# Power.net
KiCad netlist of a schematic drawn in Altium Designer
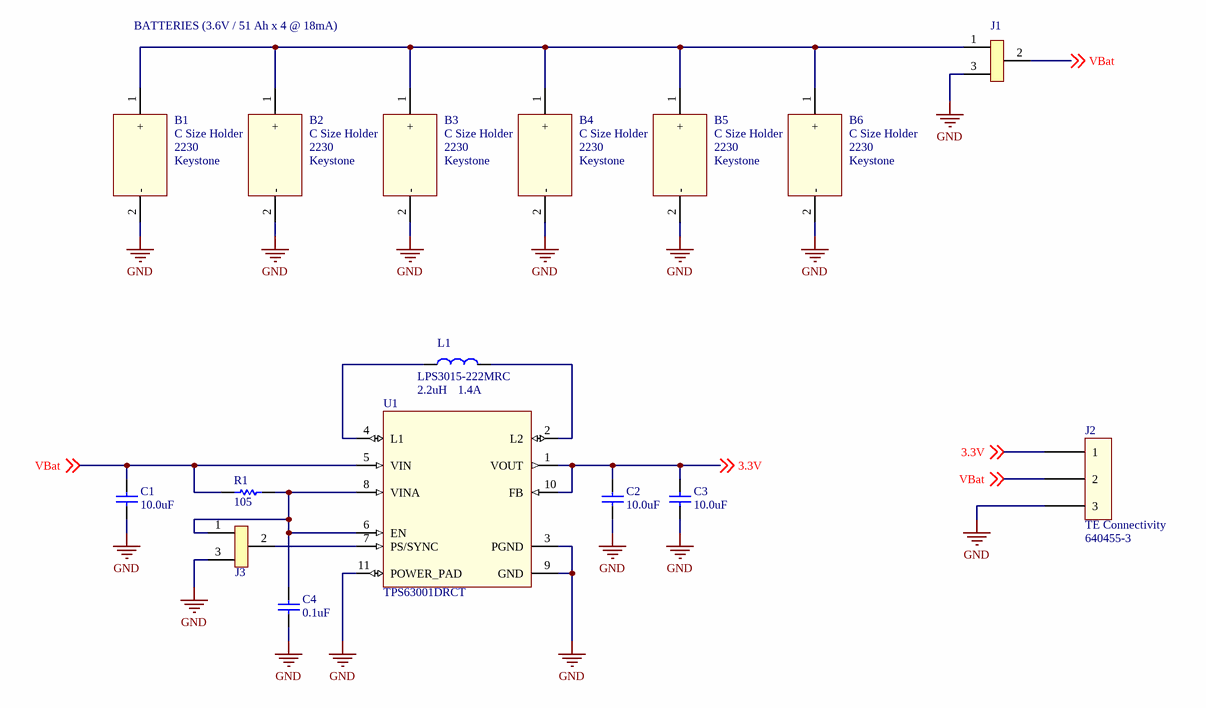
[diagram p0: Power.SchDoc]

(export (version "E")
  (design (tool "Eeschema 10.0.6"))
  (components
    (comp (ref "B1")
      (value "C Size Holder")
      (footprint "KEYSTONE-2230")
      (fields
        (field (name "PARTNUMBER") "2230")
        (field (name "MANUFACTURER") "Keystone")
        (field (name "Comment") "2230")
      )
      (libsource (lib "Keystone") (part "2230"))
    )
    (comp (ref "B2")
      (value "C Size Holder")
      (footprint "KEYSTONE-2230")
      (fields
        (field (name "PARTNUMBER") "2230")
        (field (name "MANUFACTURER") "Keystone")
        (field (name "Comment") "2230")
      )
      (libsource (lib "Keystone") (part "2230"))
    )
    (comp (ref "B3")
      (value "C Size Holder")
      (footprint "KEYSTONE-2230")
      (fields
        (field (name "PARTNUMBER") "2230")
        (field (name "MANUFACTURER") "Keystone")
        (field (name "Comment") "2230")
      )
      (libsource (lib "Keystone") (part "2230"))
    )
    (comp (ref "B4")
      (value "C Size Holder")
      (footprint "KEYSTONE-2230")
      (fields
        (field (name "PARTNUMBER") "2230")
        (field (name "MANUFACTURER") "Keystone")
        (field (name "Comment") "2230")
      )
      (libsource (lib "Keystone") (part "2230"))
    )
    (comp (ref "B5")
      (value "C Size Holder")
      (footprint "KEYSTONE-2230")
      (fields
        (field (name "PARTNUMBER") "2230")
        (field (name "MANUFACTURER") "Keystone")
        (field (name "Comment") "2230")
      )
      (libsource (lib "Keystone") (part "2230"))
    )
    (comp (ref "B6")
      (value "C Size Holder")
      (footprint "KEYSTONE-2230")
      (fields
        (field (name "PARTNUMBER") "2230")
        (field (name "MANUFACTURER") "Keystone")
        (field (name "Comment") "2230")
      )
      (libsource (lib "Keystone") (part "2230"))
    )
    (comp (ref "C1")
      (value "10.0uF")
      (footprint "CAP-0603")
      (description "CAP CER 10uF 10V X5R 0603")
      (fields (field (name "PARTNUMBER") "C0603C106M9PAC7867") (field (name "MANUFACTURER") "Kemet"))
      (libsource (lib "Kemet") (part "C0603C106M9PAC7867"))
    )
    (comp (ref "C2")
      (value "10.0uF")
      (footprint "CAP-0603")
      (description "CAP CER 10uF 10V X5R 0603")
      (fields (field (name "PARTNUMBER") "C0603C106M9PAC7867") (field (name "MANUFACTURER") "Kemet"))
      (libsource (lib "Kemet") (part "C0603C106M9PAC7867"))
    )
    (comp (ref "C3")
      (value "10.0uF")
      (footprint "CAP-0603")
      (description "CAP CER 10uF 10V X5R 0603")
      (fields (field (name "PARTNUMBER") "C0603C106M9PAC7867") (field (name "MANUFACTURER") "Kemet"))
      (libsource (lib "Kemet") (part "C0603C106M9PAC7867"))
    )
    (comp (ref "C4")
      (value "0.1uF")
      (footprint "CAP-0603")
      (description "CAP CER 0.1uF 50V X7R 0603")
      (fields (field (name "PARTNUMBER") "C0603C104K5RACAUTO") (field (name "MANUFACTURER") "Kemet"))
      (libsource (lib "Kemet") (part "C0603C104K5RACAUTO"))
    )
    (comp (ref "J1")
      (value "PRPC003SAAN-RC")
      (footprint "PIN3")
      (description "CONN HEADER .100\" SNGL STR 3POS")
      (fields (field (name "MANUFACTURER") "Sullins Connector Solutions"))
      (libsource (lib "Sullins") (part "PRPC003SAAN-RC"))
    )
    (comp (ref "J2")
      (value "640455-3")
      (footprint "TE-640455-3")
      (description "CONN HEADER RTANG 3POS .100 TIN")
      (fields (field (name "MANUFACTURER") "TE Connectivity") (field (name "PARTNUMBER") "640455-3"))
      (libsource (lib "TeConnectivity") (part "640455-3"))
    )
    (comp (ref "J3")
      (value "PRPC003SAAN-RC")
      (footprint "PIN3")
      (description "CONN HEADER .100\" SNGL STR 3POS")
      (fields (field (name "MANUFACTURER") "Sullins Connector Solutions"))
      (libsource (lib "Sullins") (part "PRPC003SAAN-RC"))
    )
    (comp (ref "L1")
      (value "LPS3015-222MRC")
      (footprint "COILCRAFT-LPS3015")
      (description "2.2 µH Shielded Inductor 1.4 A 110 mOhm")
      (fields
        (field (name "MANUFACTURER") "Coilcraft")
        (field (name "CURRENT") "1.4A")
        (field (name "ALTIUM_VALUE") "2.2uH")
      )
      (libsource (lib "Coilcraft") (part "LPS3015-222MRC"))
    )
    (comp (ref "R1")
      (value "105")
      (footprint "RES-0603")
      (description "RES SMD 105 OHM 1% 1/8W 0805")
      (fields (field (name "TOLERANCE") "1%") (field (name "MANUFACTURER") "Yageo"))
      (libsource (lib "Yageo") (part "RC0805FR-07105RL"))
    )
    (comp (ref "U1")
      (value "TPS63001DRCT")
      (footprint "VSON10")
      (description "Buck Boost Regulator 3.3V 1.6A 10VSON")
      (fields (field (name "MANUFACTURER") "Texas Instruments") (field (name "PARTNUMBER") "TPS63001DRCT"))
      (libsource (lib "TexasInstruments") (part "TPS63001DRCT"))
    )
  )
  (nets
    (net (code "1") (name "3.3V") (class "Default")
      (node (ref "C2") (pin "2") (pinfunction "2_2") (pintype "passive"))
      (node (ref "C3") (pin "2") (pinfunction "2_2") (pintype "passive"))
      (node (ref "J2") (pin "1") (pinfunction "1_1") (pintype "passive"))
      (node (ref "U1") (pin "1") (pinfunction "VOUT_1") (pintype "output"))
      (node (ref "U1") (pin "10") (pinfunction "FB_10") (pintype "input"))
    )
    (net (code "2") (name "GND") (class "Default")
      (node (ref "B1") (pin "2") (pinfunction "-_2") (pintype "passive"))
      (node (ref "B2") (pin "2") (pinfunction "-_2") (pintype "passive"))
      (node (ref "B3") (pin "2") (pinfunction "-_2") (pintype "passive"))
      (node (ref "B4") (pin "2") (pinfunction "-_2") (pintype "passive"))
      (node (ref "B5") (pin "2") (pinfunction "-_2") (pintype "passive"))
      (node (ref "B6") (pin "2") (pinfunction "-_2") (pintype "passive"))
      (node (ref "C1") (pin "1") (pinfunction "1_1") (pintype "passive"))
      (node (ref "C2") (pin "1") (pinfunction "1_1") (pintype "passive"))
      (node (ref "C3") (pin "1") (pinfunction "1_1") (pintype "passive"))
      (node (ref "C4") (pin "1") (pinfunction "1_1") (pintype "passive"))
      (node (ref "J1") (pin "3") (pinfunction "3_3") (pintype "passive"))
      (node (ref "J2") (pin "3") (pinfunction "3_3") (pintype "passive"))
      (node (ref "J3") (pin "3") (pinfunction "3_3") (pintype "passive"))
      (node (ref "U1") (pin "11") (pinfunction "POWER_PAD_11") (pintype "bidirectional"))
      (node (ref "U1") (pin "3") (pinfunction "PGND_3") (pintype "power_in"))
      (node (ref "U1") (pin "9") (pinfunction "GND_9") (pintype "power_in"))
    )
    (net (code "3") (name "Net-(B1-+)") (class "Default")
      (node (ref "B1") (pin "1") (pinfunction "+_1") (pintype "passive"))
      (node (ref "B2") (pin "1") (pinfunction "+_1") (pintype "passive"))
      (node (ref "B3") (pin "1") (pinfunction "+_1") (pintype "passive"))
      (node (ref "B4") (pin "1") (pinfunction "+_1") (pintype "passive"))
      (node (ref "B5") (pin "1") (pinfunction "+_1") (pintype "passive"))
      (node (ref "B6") (pin "1") (pinfunction "+_1") (pintype "passive"))
      (node (ref "J1") (pin "1") (pinfunction "1_1") (pintype "passive"))
    )
    (net (code "4") (name "Net-(U1-EN)") (class "Default")
      (node (ref "C4") (pin "2") (pinfunction "2_2") (pintype "passive"))
      (node (ref "J3") (pin "1") (pinfunction "1_1") (pintype "passive"))
      (node (ref "R1") (pin "2") (pinfunction "2_2") (pintype "passive"))
      (node (ref "U1") (pin "6") (pinfunction "EN_6") (pintype "input"))
      (node (ref "U1") (pin "8") (pinfunction "VINA_8") (pintype "input"))
    )
    (net (code "5") (name "Net-(U1-L1)") (class "Default")
      (node (ref "L1") (pin "1") (pinfunction "1_1") (pintype "passive"))
      (node (ref "U1") (pin "4") (pinfunction "L1_4") (pintype "bidirectional"))
    )
    (net (code "6") (name "Net-(U1-L2)") (class "Default")
      (node (ref "L1") (pin "2") (pinfunction "2_2") (pintype "passive"))
      (node (ref "U1") (pin "2") (pinfunction "L2_2") (pintype "bidirectional"))
    )
    (net (code "7") (name "Net-(U1-PS{slash}SYNC)") (class "Default")
      (node (ref "J3") (pin "2") (pinfunction "2_2") (pintype "passive"))
      (node (ref "U1") (pin "7") (pinfunction "PS/SYNC_7") (pintype "input"))
    )
    (net (code "8") (name "VBat") (class "Default")
      (node (ref "C1") (pin "2") (pinfunction "2_2") (pintype "passive"))
      (node (ref "J1") (pin "2") (pinfunction "2_2") (pintype "passive"))
      (node (ref "J2") (pin "2") (pinfunction "2_2") (pintype "passive"))
      (node (ref "R1") (pin "1") (pinfunction "1_1") (pintype "passive"))
      (node (ref "U1") (pin "5") (pinfunction "VIN_5") (pintype "input"))
    )
  )
)
